# TRV_RFM70_V0_1.net
KiCad netlist of a schematic drawn in EAGLE
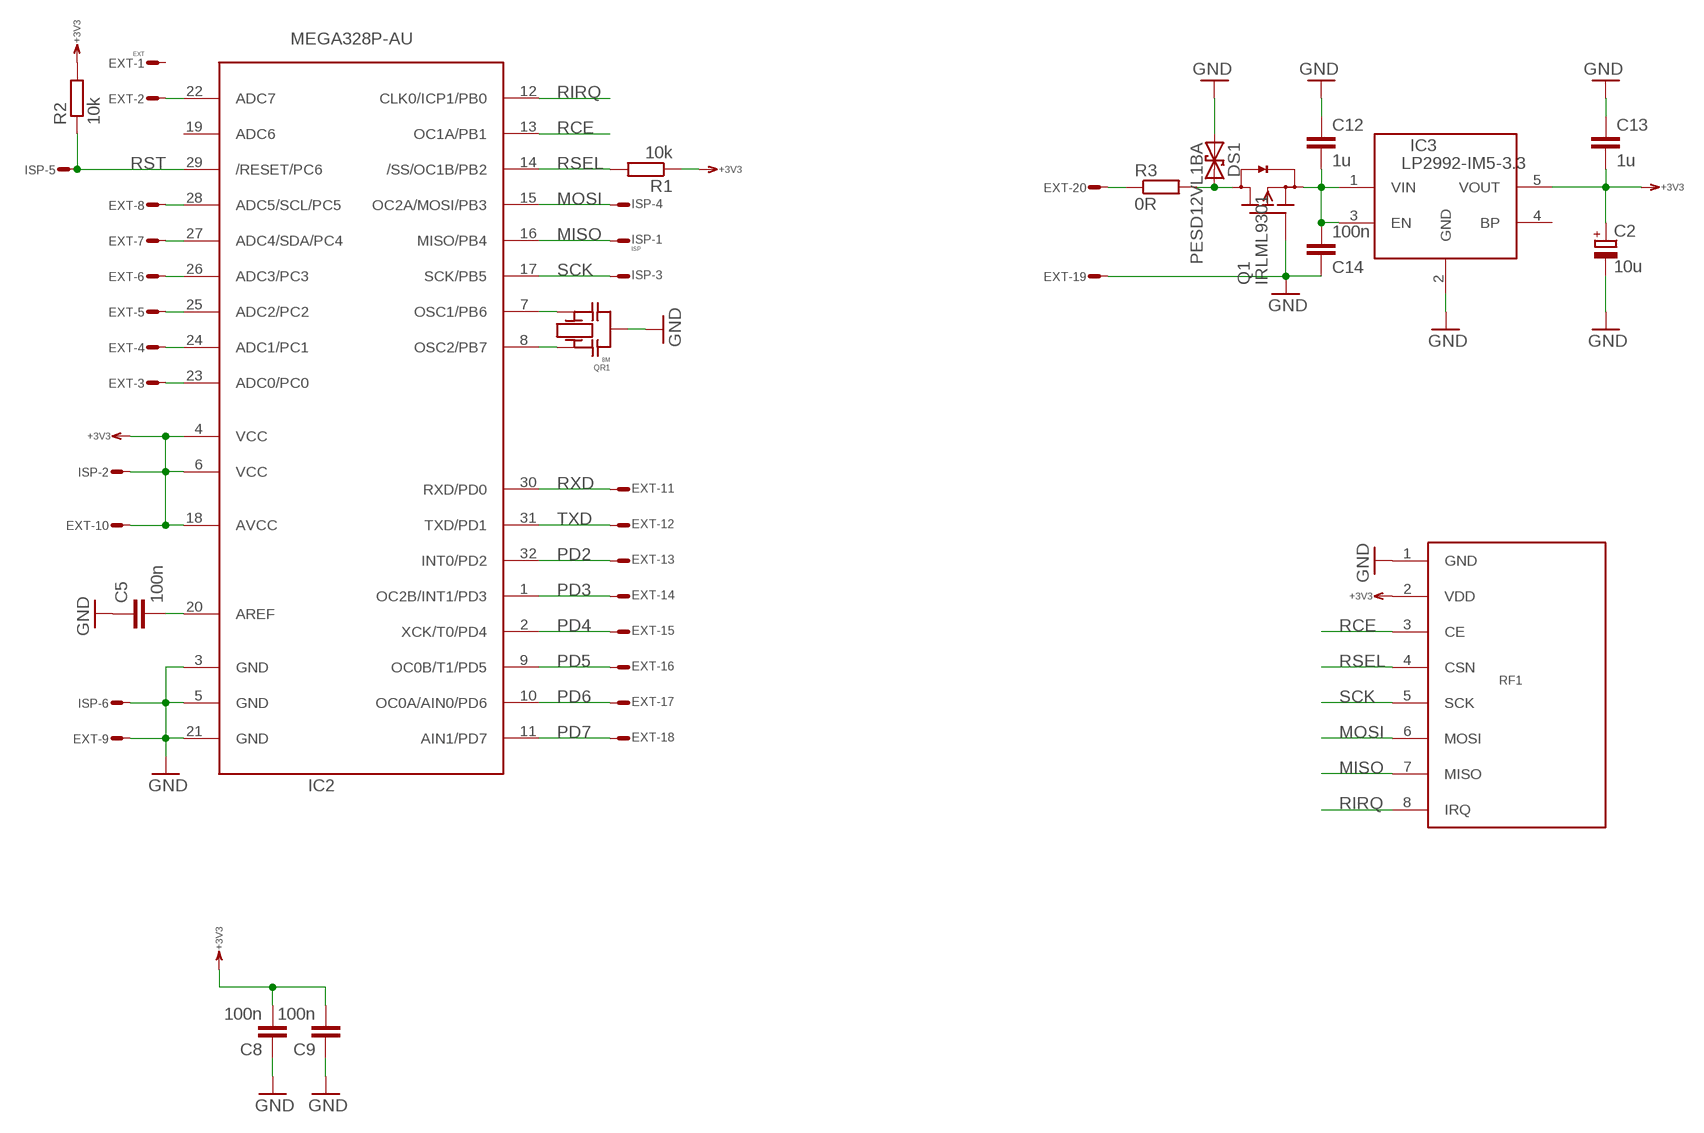
[diagram p0: schematic, sheet 1]

(export (version "E")
  (design (tool "Eeschema 10.0.6"))
  (components
    (comp (ref "C2")
      (value "10u")
      (footprint "eagle-import:SMC_B")
      (libsource (lib "eagle-import") (part "C_POLSMCB"))
    )
    (comp (ref "C5")
      (value "100n")
      (footprint "eagle-import:0603")
      (libsource (lib "eagle-import") (part "C0603"))
    )
    (comp (ref "C8")
      (value "100n")
      (footprint "eagle-import:0603")
      (libsource (lib "eagle-import") (part "C0603"))
    )
    (comp (ref "C9")
      (value "100n")
      (footprint "eagle-import:0603")
      (libsource (lib "eagle-import") (part "C0603"))
    )
    (comp (ref "C12")
      (value "1u")
      (footprint "eagle-import:0603")
      (libsource (lib "eagle-import") (part "C0603"))
    )
    (comp (ref "C13")
      (value "1u")
      (footprint "eagle-import:0603")
      (libsource (lib "eagle-import") (part "C0603"))
    )
    (comp (ref "C14")
      (value "100n")
      (footprint "eagle-import:0603")
      (libsource (lib "eagle-import") (part "C0603"))
    )
    (comp (ref "DS1")
      (value "PESD12VL1BA")
      (footprint "eagle-import:SOD323")
      (libsource (lib "eagle-import") (part "TVS-U323"))
    )
    (comp (ref "EXT")
      (value "EXT")
      (footprint "eagle-import:ML20S")
      (libsource (lib "eagle-import") (part "ML20?ES"))
    )
    (comp (ref "IC2")
      (value "MEGA328P-AU")
      (footprint "eagle-import:TQFP32-08")
      (libsource (lib "eagle-import") (part "MEGA168PA"))
    )
    (comp (ref "IC3")
      (value "LP2992-IM5-3.3")
      (footprint "eagle-import:SOT23-5")
      (libsource (lib "eagle-import") (part "LDO"))
    )
    (comp (ref "ISP")
      (value "ISP")
      (footprint "eagle-import:ML6S")
      (libsource (lib "eagle-import") (part "ML6ES"))
    )
    (comp (ref "Q1")
      (value "IRLML9301")
      (footprint "eagle-import:SOT23")
      (libsource (lib "eagle-import") (part "FET-PDSOT23"))
    )
    (comp (ref "QR1")
      (value "8M")
      (footprint "eagle-import:CR")
      (libsource (lib "eagle-import") (part "QRCR"))
    )
    (comp (ref "R1")
      (value "10k")
      (footprint "eagle-import:0603")
      (libsource (lib "eagle-import") (part "R0603"))
    )
    (comp (ref "R2")
      (value "10k")
      (footprint "eagle-import:0603")
      (libsource (lib "eagle-import") (part "R0603"))
    )
    (comp (ref "R3")
      (value "0R")
      (footprint "eagle-import:0603")
      (libsource (lib "eagle-import") (part "R0603"))
    )
    (comp (ref "RF1")
      (value "RFM70S")
      (footprint "eagle-import:RFM70D")
      (libsource (lib "eagle-import") (part "RFM70S"))
    )
  )
  (nets
    (net (code "1") (name "+3V3") (class "Default")
      (node (ref "C13") (pin "2") (pinfunction "2_2") (pintype "passive"))
      (node (ref "C2") (pin "+") (pinfunction "+_+") (pintype "passive"))
      (node (ref "C8") (pin "2") (pinfunction "2_2") (pintype "passive"))
      (node (ref "C9") (pin "2") (pinfunction "2_2") (pintype "passive"))
      (node (ref "EXT") (pin "10") (pinfunction "S_10") (pintype "passive"))
      (node (ref "IC2") (pin "18") (pinfunction "AVCC_18") (pintype "bidirectional"))
      (node (ref "IC2") (pin "4") (pinfunction "VCC_4") (pintype "bidirectional"))
      (node (ref "IC2") (pin "6") (pinfunction "VCC_6") (pintype "bidirectional"))
      (node (ref "IC3") (pin "5") (pinfunction "VOUT_5") (pintype "bidirectional"))
      (node (ref "ISP") (pin "2") (pinfunction "S_2") (pintype "passive"))
      (node (ref "R1") (pin "1") (pinfunction "1_1") (pintype "passive"))
      (node (ref "R2") (pin "2") (pinfunction "2_2") (pintype "passive"))
      (node (ref "RF1") (pin "2") (pinfunction "VDD_2") (pintype "bidirectional"))
    )
    (net (code "2") (name "/MISO") (class "Default")
      (node (ref "IC2") (pin "16") (pinfunction "MISO/PB4_16") (pintype "bidirectional"))
      (node (ref "ISP") (pin "1") (pinfunction "S_1") (pintype "passive"))
      (node (ref "RF1") (pin "7") (pinfunction "MISO_7") (pintype "bidirectional"))
    )
    (net (code "3") (name "/MOSI") (class "Default")
      (node (ref "IC2") (pin "15") (pinfunction "OC2A/MOSI/PB3_15") (pintype "bidirectional"))
      (node (ref "ISP") (pin "4") (pinfunction "S_4") (pintype "passive"))
      (node (ref "RF1") (pin "6") (pinfunction "MOSI_6") (pintype "bidirectional"))
    )
    (net (code "4") (name "/PD2") (class "Default")
      (node (ref "EXT") (pin "13") (pinfunction "S_13") (pintype "passive"))
      (node (ref "IC2") (pin "32") (pinfunction "INT0/PD2_32") (pintype "bidirectional"))
    )
    (net (code "5") (name "/PD3") (class "Default")
      (node (ref "EXT") (pin "14") (pinfunction "S_14") (pintype "passive"))
      (node (ref "IC2") (pin "1") (pinfunction "OC2B/INT1/PD3_1") (pintype "bidirectional"))
    )
    (net (code "6") (name "/PD4") (class "Default")
      (node (ref "EXT") (pin "15") (pinfunction "S_15") (pintype "passive"))
      (node (ref "IC2") (pin "2") (pinfunction "XCK/T0/PD4_2") (pintype "bidirectional"))
    )
    (net (code "7") (name "/PD5") (class "Default")
      (node (ref "EXT") (pin "16") (pinfunction "S_16") (pintype "passive"))
      (node (ref "IC2") (pin "9") (pinfunction "OC0B/T1/PD5_9") (pintype "bidirectional"))
    )
    (net (code "8") (name "/PD6") (class "Default")
      (node (ref "EXT") (pin "17") (pinfunction "S_17") (pintype "passive"))
      (node (ref "IC2") (pin "10") (pinfunction "OC0A/AIN0/PD6_10") (pintype "bidirectional"))
    )
    (net (code "9") (name "/PD7") (class "Default")
      (node (ref "EXT") (pin "18") (pinfunction "S_18") (pintype "passive"))
      (node (ref "IC2") (pin "11") (pinfunction "AIN1/PD7_11") (pintype "bidirectional"))
    )
    (net (code "10") (name "/RCE") (class "Default")
      (node (ref "IC2") (pin "13") (pinfunction "OC1A/PB1_13") (pintype "bidirectional"))
      (node (ref "RF1") (pin "3") (pinfunction "CE_3") (pintype "bidirectional"))
    )
    (net (code "11") (name "/RIRQ") (class "Default")
      (node (ref "IC2") (pin "12") (pinfunction "CLK0/ICP1/PB0_12") (pintype "bidirectional"))
      (node (ref "RF1") (pin "8") (pinfunction "IRQ_8") (pintype "bidirectional"))
    )
    (net (code "12") (name "/RSEL") (class "Default")
      (node (ref "IC2") (pin "14") (pinfunction "/SS/OC1B/PB2_14") (pintype "bidirectional"))
      (node (ref "R1") (pin "2") (pinfunction "2_2") (pintype "passive"))
      (node (ref "RF1") (pin "4") (pinfunction "CSN_4") (pintype "bidirectional"))
    )
    (net (code "13") (name "/RST") (class "Default")
      (node (ref "IC2") (pin "29") (pinfunction "/RESET/PC6_29") (pintype "bidirectional"))
      (node (ref "ISP") (pin "5") (pinfunction "S_5") (pintype "passive"))
      (node (ref "R2") (pin "1") (pinfunction "1_1") (pintype "passive"))
    )
    (net (code "14") (name "/RXD") (class "Default")
      (node (ref "EXT") (pin "11") (pinfunction "S_11") (pintype "passive"))
      (node (ref "IC2") (pin "30") (pinfunction "RXD/PD0_30") (pintype "bidirectional"))
    )
    (net (code "15") (name "/SCK") (class "Default")
      (node (ref "IC2") (pin "17") (pinfunction "SCK/PB5_17") (pintype "bidirectional"))
      (node (ref "ISP") (pin "3") (pinfunction "S_3") (pintype "passive"))
      (node (ref "RF1") (pin "5") (pinfunction "SCK_5") (pintype "bidirectional"))
    )
    (net (code "16") (name "/TXD") (class "Default")
      (node (ref "EXT") (pin "12") (pinfunction "S_12") (pintype "passive"))
      (node (ref "IC2") (pin "31") (pinfunction "TXD/PD1_31") (pintype "bidirectional"))
    )
    (net (code "17") (name "GND") (class "Default")
      (node (ref "C12") (pin "1") (pinfunction "1_1") (pintype "passive"))
      (node (ref "C13") (pin "1") (pinfunction "1_1") (pintype "passive"))
      (node (ref "C14") (pin "1") (pinfunction "1_1") (pintype "passive"))
      (node (ref "C2") (pin "-") (pinfunction "-_-") (pintype "passive"))
      (node (ref "C5") (pin "1") (pinfunction "1_1") (pintype "passive"))
      (node (ref "C8") (pin "1") (pinfunction "1_1") (pintype "passive"))
      (node (ref "C9") (pin "1") (pinfunction "1_1") (pintype "passive"))
      (node (ref "DS1") (pin "A") (pinfunction "1_A") (pintype "passive"))
      (node (ref "EXT") (pin "19") (pinfunction "S_19") (pintype "passive"))
      (node (ref "EXT") (pin "9") (pinfunction "S_9") (pintype "passive"))
      (node (ref "IC2") (pin "21") (pinfunction "GND_21") (pintype "bidirectional"))
      (node (ref "IC2") (pin "3") (pinfunction "GND_3") (pintype "bidirectional"))
      (node (ref "IC2") (pin "5") (pinfunction "GND_5") (pintype "bidirectional"))
      (node (ref "IC3") (pin "2") (pinfunction "GND_2") (pintype "bidirectional"))
      (node (ref "ISP") (pin "6") (pinfunction "S_6") (pintype "passive"))
      (node (ref "Q1") (pin "1") (pinfunction "G_1") (pintype "passive"))
      (node (ref "QR1") (pin "M") (pinfunction "M_M") (pintype "passive"))
      (node (ref "RF1") (pin "1") (pinfunction "GND_1") (pintype "bidirectional"))
    )
    (net (code "18") (name "Net-(DS1-2)") (class "Default")
      (node (ref "DS1") (pin "C") (pinfunction "2_C") (pintype "passive"))
      (node (ref "Q1") (pin "3") (pinfunction "D_3") (pintype "passive"))
      (node (ref "R3") (pin "2") (pinfunction "2_2") (pintype "passive"))
    )
    (net (code "19") (name "Net-(EXTL-S)") (class "Default")
      (node (ref "EXT") (pin "2") (pinfunction "S_2") (pintype "passive"))
      (node (ref "IC2") (pin "22") (pinfunction "ADC7_22") (pintype "bidirectional"))
    )
    (net (code "20") (name "Net-(EXTM-S)") (class "Default")
      (node (ref "EXT") (pin "20") (pinfunction "S_20") (pintype "passive"))
      (node (ref "R3") (pin "1") (pinfunction "1_1") (pintype "passive"))
    )
    (net (code "21") (name "Net-(EXTN-S)") (class "Default")
      (node (ref "EXT") (pin "3") (pinfunction "S_3") (pintype "passive"))
      (node (ref "IC2") (pin "23") (pinfunction "ADC0/PC0_23") (pintype "bidirectional"))
    )
    (net (code "22") (name "Net-(EXTO-S)") (class "Default")
      (node (ref "EXT") (pin "4") (pinfunction "S_4") (pintype "passive"))
      (node (ref "IC2") (pin "24") (pinfunction "ADC1/PC1_24") (pintype "bidirectional"))
    )
    (net (code "23") (name "Net-(EXTP-S)") (class "Default")
      (node (ref "EXT") (pin "5") (pinfunction "S_5") (pintype "passive"))
      (node (ref "IC2") (pin "25") (pinfunction "ADC2/PC2_25") (pintype "bidirectional"))
    )
    (net (code "24") (name "Net-(EXTQ-S)") (class "Default")
      (node (ref "EXT") (pin "6") (pinfunction "S_6") (pintype "passive"))
      (node (ref "IC2") (pin "26") (pinfunction "ADC3/PC3_26") (pintype "bidirectional"))
    )
    (net (code "25") (name "Net-(EXTR-S)") (class "Default")
      (node (ref "EXT") (pin "7") (pinfunction "S_7") (pintype "passive"))
      (node (ref "IC2") (pin "27") (pinfunction "ADC4/SDA/PC4_27") (pintype "bidirectional"))
    )
    (net (code "26") (name "Net-(EXTS-S)") (class "Default")
      (node (ref "EXT") (pin "8") (pinfunction "S_8") (pintype "passive"))
      (node (ref "IC2") (pin "28") (pinfunction "ADC5/SCL/PC5_28") (pintype "bidirectional"))
    )
    (net (code "27") (name "Net-(IC2-AREF)") (class "Default")
      (node (ref "C5") (pin "2") (pinfunction "2_2") (pintype "passive"))
      (node (ref "IC2") (pin "20") (pinfunction "AREF_20") (pintype "bidirectional"))
    )
    (net (code "28") (name "Net-(IC2-OSC1{slash}PB6)") (class "Default")
      (node (ref "IC2") (pin "7") (pinfunction "OSC1/PB6_7") (pintype "bidirectional"))
      (node (ref "QR1") (pin "2") (pinfunction "2_2") (pintype "passive"))
    )
    (net (code "29") (name "Net-(IC2-OSC2{slash}PB7)") (class "Default")
      (node (ref "IC2") (pin "8") (pinfunction "OSC2/PB7_8") (pintype "bidirectional"))
      (node (ref "QR1") (pin "1") (pinfunction "1_1") (pintype "passive"))
    )
    (net (code "30") (name "Net-(IC3-EN)") (class "Default")
      (node (ref "C12") (pin "2") (pinfunction "2_2") (pintype "passive"))
      (node (ref "C14") (pin "2") (pinfunction "2_2") (pintype "passive"))
      (node (ref "IC3") (pin "1") (pinfunction "VIN_1") (pintype "bidirectional"))
      (node (ref "IC3") (pin "3") (pinfunction "EN_3") (pintype "bidirectional"))
      (node (ref "Q1") (pin "2") (pinfunction "S_2") (pintype "passive"))
    )
    (net (code "31") (name "unconnected-(EXTA-S-Pad1)") (class "Default")
      (node (ref "EXT") (pin "1") (pinfunction "S_1") (pintype "passive"))
    )
    (net (code "32") (name "unconnected-(IC2-ADC6-Pad19)") (class "Default")
      (node (ref "IC2") (pin "19") (pinfunction "ADC6_19") (pintype "bidirectional"))
    )
    (net (code "33") (name "unconnected-(IC3-BP-Pad4)") (class "Default")
      (node (ref "IC3") (pin "4") (pinfunction "BP_4") (pintype "bidirectional"))
    )
  )
)
